# SparkFun_Cellular_Shield.net
KiCad netlist of a schematic drawn in EAGLE
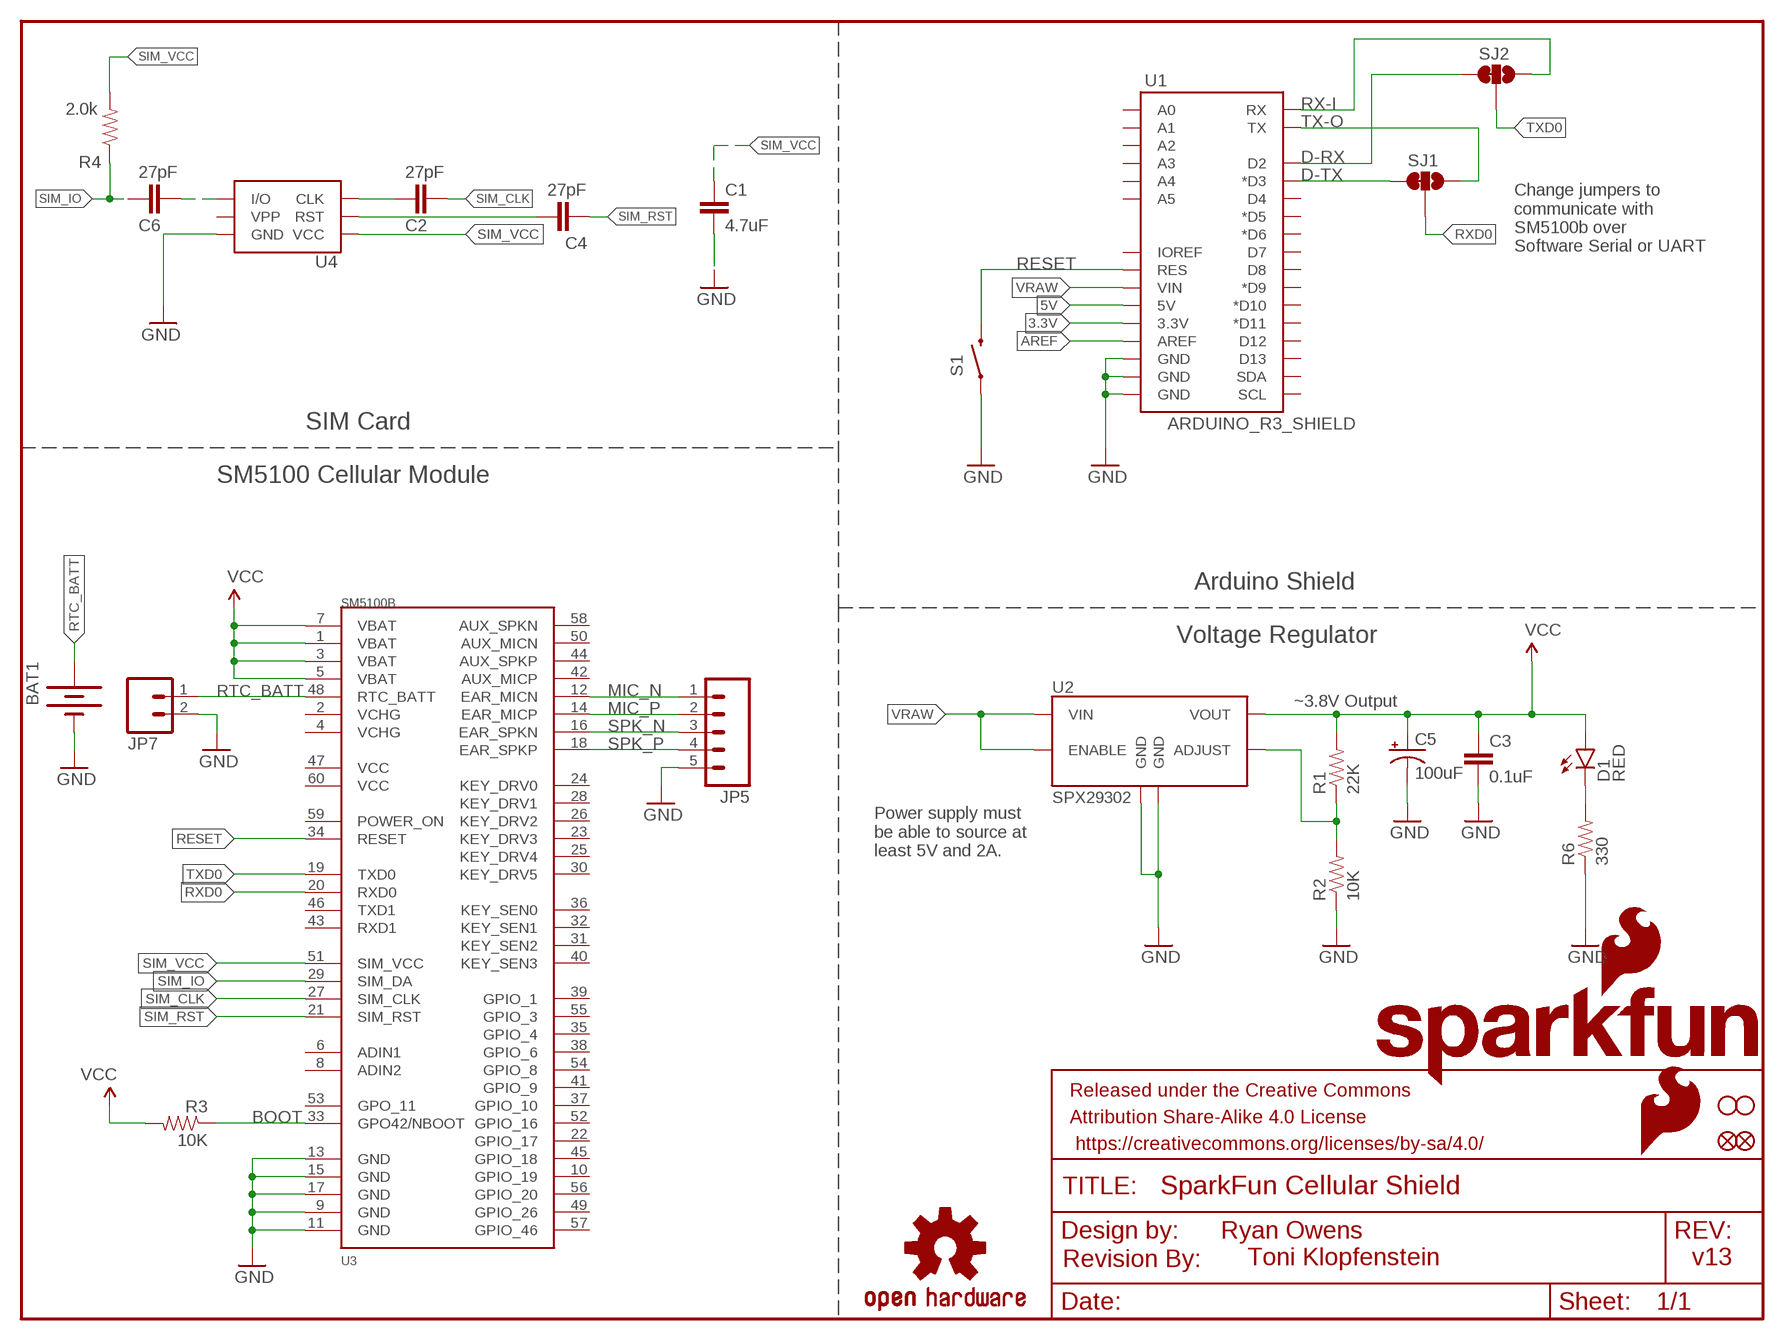
[diagram p0: schematic, sheet 1]

(export (version "E")
  (design (tool "Eeschema 10.0.6"))
  (components
    (comp (ref "BAT1")
      (value "BATTERY20SMD")
      (footprint "eagle-import:BATTCON_20MM")
      (libsource (lib "eagle-import") (part "BATTERY20SMD"))
    )
    (comp (ref "C1")
      (value "4.7uF")
      (footprint "eagle-import:0603-CAP")
      (libsource (lib "eagle-import") (part "4.7UF-6.3V-10%(0603)0603"))
    )
    (comp (ref "C2")
      (value "27pF")
      (footprint "eagle-import:0603-CAP")
      (libsource (lib "eagle-import") (part "27PF50V5%(0603)"))
    )
    (comp (ref "C3")
      (value "0.1uF")
      (footprint "eagle-import:0603-CAP")
      (libsource (lib "eagle-import") (part "0.1UF-25V(+80/-20%)(0603)"))
    )
    (comp (ref "C4")
      (value "27pF")
      (footprint "eagle-import:0603-CAP")
      (libsource (lib "eagle-import") (part "27PF50V5%(0603)"))
    )
    (comp (ref "C5")
      (value "100uF")
      (footprint "eagle-import:EIA7343")
      (libsource (lib "eagle-import") (part "100UF-10V-10%(TANT)"))
    )
    (comp (ref "C6")
      (value "27pF")
      (footprint "eagle-import:0603-CAP")
      (libsource (lib "eagle-import") (part "27PF50V5%(0603)"))
    )
    (comp (ref "D1")
      (value "RED")
      (footprint "eagle-import:LED-0603")
      (libsource (lib "eagle-import") (part "LED-RED0603"))
    )
    (comp (ref "FRAME1")
      (value "FRAME-LETTER")
      (footprint "eagle-import:CREATIVE_COMMONS")
      (libsource (lib "eagle-import") (part "FRAME-LETTER"))
    )
    (comp (ref "JP1")
      (value "SFE_LOGO_NAME_FLAME.2_INCH")
      (footprint "eagle-import:SFE_LOGO_NAME_FLAME_.2")
      (libsource (lib "eagle-import") (part "SFE_LOGO_NAME_FLAME.2_INCH"))
    )
    (comp (ref "JP2")
      (value "FIDUCIAL1X2")
      (footprint "eagle-import:FIDUCIAL-1X2")
      (libsource (lib "eagle-import") (part "FIDUCIAL1X2"))
    )
    (comp (ref "JP3")
      (value "FIDUCIAL1X2")
      (footprint "eagle-import:FIDUCIAL-1X2")
      (libsource (lib "eagle-import") (part "FIDUCIAL1X2"))
    )
    (comp (ref "JP5")
      (value "M05PTH")
      (footprint "eagle-import:1X05")
      (libsource (lib "eagle-import") (part "M05PTH"))
    )
    (comp (ref "JP7")
      (value "M02PTH")
      (footprint "eagle-import:1X02")
      (libsource (lib "eagle-import") (part "M02PTH"))
    )
    (comp (ref "LOGO1")
      (value "OSHW-LOGOM")
      (footprint "eagle-import:OSHW-LOGO-M")
      (libsource (lib "eagle-import") (part "OSHW-LOGOM"))
    )
    (comp (ref "LOGO2")
      (value "SFE_LOGO_FLAME.1_INCH")
      (footprint "eagle-import:SFE_LOGO_FLAME_.1")
      (libsource (lib "eagle-import") (part "SFE_LOGO_FLAME.1_INCH"))
    )
    (comp (ref "R1")
      (value "22K")
      (footprint "eagle-import:0603-RES")
      (libsource (lib "eagle-import") (part "22KOHM1/10W1%(0603)"))
    )
    (comp (ref "R2")
      (value "10K")
      (footprint "eagle-import:0603-RES")
      (libsource (lib "eagle-import") (part "10KOHM-1/10W-1%(0603)0603"))
    )
    (comp (ref "R3")
      (value "10K")
      (footprint "eagle-import:0603-RES")
      (libsource (lib "eagle-import") (part "10KOHM-1/10W-1%(0603)0603"))
    )
    (comp (ref "R4")
      (value "2.0k")
      (footprint "eagle-import:0603-RES")
      (libsource (lib "eagle-import") (part "2.0KOHM1/10W5%(0603)"))
    )
    (comp (ref "R6")
      (value "330")
      (footprint "eagle-import:0603-RES")
      (libsource (lib "eagle-import") (part "330OHM1/10W1%(0603)"))
    )
    (comp (ref "S1")
      (value "TAC_SWITCHSMD")
      (footprint "eagle-import:TACTILE-SWITCH-SMD")
      (libsource (lib "eagle-import") (part "SWITCH-MOMENTARY-2SMD"))
    )
    (comp (ref "SJ1")
      (value "JUMPER-PAD-3-2OF3_NC_BY_TRACE_SMALL")
      (footprint "eagle-import:PAD-JUMPER-3-2OF3_NC_BY_TRACE_YES_SILK_FULL_BOX")
      (libsource (lib "eagle-import") (part "JUMPER-PAD-3-2OF3_NC_BY_TRACE_SMALL"))
    )
    (comp (ref "SJ2")
      (value "JUMPER-PAD-3-2OF3_NC_BY_TRACE_SMALL")
      (footprint "eagle-import:PAD-JUMPER-3-2OF3_NC_BY_TRACE_YES_SILK_FULL_BOX")
      (libsource (lib "eagle-import") (part "JUMPER-PAD-3-2OF3_NC_BY_TRACE_SMALL"))
    )
    (comp (ref "STANDOFF1")
      (value "STAND-OFF")
      (footprint "eagle-import:STAND-OFF")
      (libsource (lib "eagle-import") (part "STAND-OFF"))
    )
    (comp (ref "STANDOFF2")
      (value "STAND-OFF")
      (footprint "eagle-import:STAND-OFF")
      (libsource (lib "eagle-import") (part "STAND-OFF"))
    )
    (comp (ref "U$1")
      (value "REVISION")
      (footprint "eagle-import:REVISION")
      (libsource (lib "eagle-import") (part "REVISION"))
    )
    (comp (ref "U1")
      (value "ARDUINO_R3_SHIELD")
      (footprint "eagle-import:UNO_R3_SHIELD")
      (libsource (lib "eagle-import") (part "ARDUINO_R3_SHIELD"))
    )
    (comp (ref "U2")
      (value "SPX29302")
      (footprint "eagle-import:Q5-DD_SPX29300")
      (libsource (lib "eagle-import") (part "SPX29302"))
    )
    (comp (ref "U3")
      (value "SM5100B")
      (footprint "eagle-import:SM5100B")
      (libsource (lib "eagle-import") (part "SM5100B"))
    )
    (comp (ref "U4")
      (value "SIMHOLDERSIM")
      (footprint "eagle-import:SIMHOLDER")
      (libsource (lib "eagle-import") (part "SIMHOLDERSIM"))
    )
  )
  (nets
    (net (code "1") (name "/BOOT") (class "Default")
      (node (ref "R3") (pin "1") (pinfunction "1_1") (pintype "passive"))
      (node (ref "U3") (pin "33") (pinfunction "GPO42/NBOOT_33") (pintype "bidirectional"))
    )
    (net (code "2") (name "/D-RX") (class "Default")
      (node (ref "SJ2") (pin "3") (pinfunction "3_3") (pintype "passive"))
      (node (ref "U1") (pin "D2") (pinfunction "D2_D2") (pintype "bidirectional"))
    )
    (net (code "3") (name "/D-TX") (class "Default")
      (node (ref "SJ1") (pin "3") (pinfunction "3_3") (pintype "passive"))
      (node (ref "U1") (pin "D3") (pinfunction "*D3_D3") (pintype "bidirectional"))
    )
    (net (code "4") (name "/MIC_N") (class "Default")
      (node (ref "JP5") (pin "1") (pinfunction "1_1") (pintype "passive"))
      (node (ref "U3") (pin "12") (pinfunction "EAR_MICN_12") (pintype "bidirectional"))
    )
    (net (code "5") (name "/MIC_P") (class "Default")
      (node (ref "JP5") (pin "2") (pinfunction "2_2") (pintype "passive"))
      (node (ref "U3") (pin "14") (pinfunction "EAR_MICP_14") (pintype "bidirectional"))
    )
    (net (code "6") (name "/RX-I") (class "Default")
      (node (ref "SJ2") (pin "1") (pinfunction "1_1") (pintype "passive"))
      (node (ref "U1") (pin "RX") (pinfunction "RX_RX") (pintype "bidirectional"))
    )
    (net (code "7") (name "/SPK_N") (class "Default")
      (node (ref "JP5") (pin "3") (pinfunction "3_3") (pintype "passive"))
      (node (ref "U3") (pin "16") (pinfunction "EAR_SPKN_16") (pintype "bidirectional"))
    )
    (net (code "8") (name "/SPK_P") (class "Default")
      (node (ref "JP5") (pin "4") (pinfunction "4_4") (pintype "passive"))
      (node (ref "U3") (pin "18") (pinfunction "EAR_SPKP_18") (pintype "bidirectional"))
    )
    (net (code "9") (name "/TX-O") (class "Default")
      (node (ref "SJ1") (pin "1") (pinfunction "1_1") (pintype "passive"))
      (node (ref "U1") (pin "TX") (pinfunction "TX_TX") (pintype "bidirectional"))
    )
    (net (code "10") (name "3.3V") (class "Default")
      (node (ref "U1") (pin "3.3V") (pinfunction "3.3V_3.3V") (pintype "bidirectional"))
    )
    (net (code "11") (name "5V") (class "Default")
      (node (ref "U1") (pin "5V") (pinfunction "5V_5V") (pintype "bidirectional"))
    )
    (net (code "12") (name "AREF") (class "Default")
      (node (ref "U1") (pin "AREF") (pinfunction "AREF_AREF") (pintype "bidirectional"))
    )
    (net (code "13") (name "GND") (class "Default")
      (node (ref "BAT1") (pin "2") (pinfunction "-_2") (pintype "power_in"))
      (node (ref "C1") (pin "2") (pinfunction "2_2") (pintype "passive"))
      (node (ref "C3") (pin "2") (pinfunction "2_2") (pintype "passive"))
      (node (ref "C5") (pin "C") (pinfunction "-_C") (pintype "passive"))
      (node (ref "JP5") (pin "5") (pinfunction "5_5") (pintype "passive"))
      (node (ref "JP7") (pin "2") (pinfunction "2_2") (pintype "passive"))
      (node (ref "R2") (pin "1") (pinfunction "1_1") (pintype "passive"))
      (node (ref "R6") (pin "1") (pinfunction "1_1") (pintype "passive"))
      (node (ref "S1") (pin "1") (pinfunction "1_1") (pintype "passive"))
      (node (ref "U1") (pin "GND@0") (pinfunction "GND_GND@0") (pintype "bidirectional"))
      (node (ref "U1") (pin "GND@1") (pinfunction "GND_GND@1") (pintype "bidirectional"))
      (node (ref "U1") (pin "GND@2") (pinfunction "GND_GND@2") (pintype "bidirectional"))
      (node (ref "U2") (pin "3") (pinfunction "GND_3") (pintype "bidirectional"))
      (node (ref "U2") (pin "6") (pinfunction "GND_6") (pintype "bidirectional"))
      (node (ref "U3") (pin "11") (pinfunction "GND_11") (pintype "bidirectional"))
      (node (ref "U3") (pin "13") (pinfunction "GND_13") (pintype "bidirectional"))
      (node (ref "U3") (pin "15") (pinfunction "GND_15") (pintype "bidirectional"))
      (node (ref "U3") (pin "17") (pinfunction "GND_17") (pintype "bidirectional"))
      (node (ref "U3") (pin "9") (pinfunction "GND_9") (pintype "bidirectional"))
      (node (ref "U4") (pin "C5") (pinfunction "GND_C5") (pintype "power_in"))
    )
    (net (code "14") (name "Net-(D1-PadC)") (class "Default")
      (node (ref "D1") (pin "C") (pinfunction "C_C") (pintype "passive"))
      (node (ref "R6") (pin "2") (pinfunction "2_2") (pintype "passive"))
    )
    (net (code "15") (name "Net-(U2-ADJUST)") (class "Default")
      (node (ref "R1") (pin "1") (pinfunction "1_1") (pintype "passive"))
      (node (ref "R2") (pin "2") (pinfunction "2_2") (pintype "passive"))
      (node (ref "U2") (pin "5") (pinfunction "ADJUST_5") (pintype "bidirectional"))
    )
    (net (code "16") (name "Net-(U4-CLK)") (class "Default")
      (node (ref "C2") (pin "2") (pinfunction "2_2") (pintype "passive"))
      (node (ref "U4") (pin "C3") (pinfunction "CLK_C3") (pintype "input"))
    )
    (net (code "17") (name "Net-(U4-I{slash}O)") (class "Default")
      (node (ref "C6") (pin "1") (pinfunction "1_1") (pintype "passive"))
      (node (ref "U4") (pin "C7") (pinfunction "I/O_C7") (pintype "bidirectional"))
    )
    (net (code "18") (name "Net-(U4-RST)") (class "Default")
      (node (ref "C4") (pin "2") (pinfunction "2_2") (pintype "passive"))
      (node (ref "U4") (pin "C2") (pinfunction "RST_C2") (pintype "input"))
    )
    (net (code "19") (name "RESET") (class "Default")
      (node (ref "S1") (pin "3") (pinfunction "2_3") (pintype "passive"))
      (node (ref "U1") (pin "RES") (pinfunction "RES_RES") (pintype "bidirectional"))
      (node (ref "U3") (pin "34") (pinfunction "RESET_34") (pintype "bidirectional"))
    )
    (net (code "20") (name "RTC_BATT") (class "Default")
      (node (ref "BAT1") (pin "1") (pinfunction "+_1") (pintype "power_in"))
      (node (ref "JP7") (pin "1") (pinfunction "1_1") (pintype "passive"))
      (node (ref "U3") (pin "48") (pinfunction "RTC_BATT_48") (pintype "bidirectional"))
    )
    (net (code "21") (name "RXD0") (class "Default")
      (node (ref "SJ1") (pin "2") (pinfunction "2_2") (pintype "passive"))
      (node (ref "U3") (pin "20") (pinfunction "RXD0_20") (pintype "bidirectional"))
    )
    (net (code "22") (name "SIM_CLK") (class "Default")
      (node (ref "C2") (pin "1") (pinfunction "1_1") (pintype "passive"))
      (node (ref "U3") (pin "27") (pinfunction "SIM_CLK_27") (pintype "bidirectional"))
    )
    (net (code "23") (name "SIM_IO") (class "Default")
      (node (ref "C6") (pin "2") (pinfunction "2_2") (pintype "passive"))
      (node (ref "R4") (pin "1") (pinfunction "1_1") (pintype "passive"))
      (node (ref "U3") (pin "29") (pinfunction "SIM_DA_29") (pintype "bidirectional"))
    )
    (net (code "24") (name "SIM_RST") (class "Default")
      (node (ref "C4") (pin "1") (pinfunction "1_1") (pintype "passive"))
      (node (ref "U3") (pin "21") (pinfunction "SIM_RST_21") (pintype "bidirectional"))
    )
    (net (code "25") (name "SIM_VCC") (class "Default")
      (node (ref "C1") (pin "1") (pinfunction "1_1") (pintype "passive"))
      (node (ref "R4") (pin "2") (pinfunction "2_2") (pintype "passive"))
      (node (ref "U3") (pin "51") (pinfunction "SIM_VCC_51") (pintype "bidirectional"))
      (node (ref "U4") (pin "C1") (pinfunction "VCC_C1") (pintype "power_in"))
    )
    (net (code "26") (name "TXD0") (class "Default")
      (node (ref "SJ2") (pin "2") (pinfunction "2_2") (pintype "passive"))
      (node (ref "U3") (pin "19") (pinfunction "TXD0_19") (pintype "bidirectional"))
    )
    (net (code "27") (name "VCC") (class "Default")
      (node (ref "C3") (pin "1") (pinfunction "1_1") (pintype "passive"))
      (node (ref "C5") (pin "A") (pinfunction "+_A") (pintype "passive"))
      (node (ref "D1") (pin "A") (pinfunction "A_A") (pintype "passive"))
      (node (ref "R1") (pin "2") (pinfunction "2_2") (pintype "passive"))
      (node (ref "R3") (pin "2") (pinfunction "2_2") (pintype "passive"))
      (node (ref "U2") (pin "4") (pinfunction "VOUT_4") (pintype "bidirectional"))
      (node (ref "U3") (pin "1") (pinfunction "VBAT_1") (pintype "bidirectional"))
      (node (ref "U3") (pin "3") (pinfunction "VBAT_3") (pintype "bidirectional"))
      (node (ref "U3") (pin "5") (pinfunction "VBAT_5") (pintype "bidirectional"))
      (node (ref "U3") (pin "7") (pinfunction "VBAT_7") (pintype "bidirectional"))
    )
    (net (code "28") (name "VRAW") (class "Default")
      (node (ref "U1") (pin "VIN") (pinfunction "VIN_VIN") (pintype "bidirectional"))
      (node (ref "U2") (pin "1") (pinfunction "ENABLE_1") (pintype "bidirectional"))
      (node (ref "U2") (pin "2") (pinfunction "VIN_2") (pintype "bidirectional"))
    )
    (net (code "29") (name "unconnected-(U1-*D5-PadD5)") (class "Default")
      (node (ref "U1") (pin "D5") (pinfunction "*D5_D5") (pintype "bidirectional"))
    )
    (net (code "30") (name "unconnected-(U1-*D6-PadD6)") (class "Default")
      (node (ref "U1") (pin "D6") (pinfunction "*D6_D6") (pintype "bidirectional"))
    )
    (net (code "31") (name "unconnected-(U1-*D9-PadD9)") (class "Default")
      (node (ref "U1") (pin "D9") (pinfunction "*D9_D9") (pintype "bidirectional"))
    )
    (net (code "32") (name "unconnected-(U1-*D10-PadD10)") (class "Default")
      (node (ref "U1") (pin "D10") (pinfunction "*D10_D10") (pintype "bidirectional"))
    )
    (net (code "33") (name "unconnected-(U1-*D11-PadD11)") (class "Default")
      (node (ref "U1") (pin "D11") (pinfunction "*D11_D11") (pintype "bidirectional"))
    )
    (net (code "34") (name "unconnected-(U1-PadA0)") (class "Default")
      (node (ref "U1") (pin "A0") (pinfunction "A0_A0") (pintype "bidirectional"))
    )
    (net (code "35") (name "unconnected-(U1-PadA1)") (class "Default")
      (node (ref "U1") (pin "A1") (pinfunction "A1_A1") (pintype "bidirectional"))
    )
    (net (code "36") (name "unconnected-(U1-PadA2)") (class "Default")
      (node (ref "U1") (pin "A2") (pinfunction "A2_A2") (pintype "bidirectional"))
    )
    (net (code "37") (name "unconnected-(U1-PadA3)") (class "Default")
      (node (ref "U1") (pin "A3") (pinfunction "A3_A3") (pintype "bidirectional"))
    )
    (net (code "38") (name "unconnected-(U1-PadA4)") (class "Default")
      (node (ref "U1") (pin "A4") (pinfunction "A4_A4") (pintype "bidirectional"))
    )
    (net (code "39") (name "unconnected-(U1-PadA5)") (class "Default")
      (node (ref "U1") (pin "A5") (pinfunction "A5_A5") (pintype "bidirectional"))
    )
    (net (code "40") (name "unconnected-(U1-PadD4)") (class "Default")
      (node (ref "U1") (pin "D4") (pinfunction "D4_D4") (pintype "bidirectional"))
    )
    (net (code "41") (name "unconnected-(U1-PadD7)") (class "Default")
      (node (ref "U1") (pin "D7") (pinfunction "D7_D7") (pintype "bidirectional"))
    )
    (net (code "42") (name "unconnected-(U1-PadD8)") (class "Default")
      (node (ref "U1") (pin "D8") (pinfunction "D8_D8") (pintype "bidirectional"))
    )
    (net (code "43") (name "unconnected-(U1-PadD12)") (class "Default")
      (node (ref "U1") (pin "D12") (pinfunction "D12_D12") (pintype "bidirectional"))
    )
    (net (code "44") (name "unconnected-(U1-PadD13)") (class "Default")
      (node (ref "U1") (pin "D13") (pinfunction "D13_D13") (pintype "bidirectional"))
    )
    (net (code "45") (name "unconnected-(U1-PadIOREF)") (class "Default")
      (node (ref "U1") (pin "IOREF") (pinfunction "IOREF_IOREF") (pintype "bidirectional"))
    )
    (net (code "46") (name "unconnected-(U1-PadSCL)") (class "Default")
      (node (ref "U1") (pin "SCL") (pinfunction "SCL_SCL") (pintype "bidirectional"))
    )
    (net (code "47") (name "unconnected-(U1-PadSDA)") (class "Default")
      (node (ref "U1") (pin "SDA") (pinfunction "SDA_SDA") (pintype "bidirectional"))
    )
    (net (code "48") (name "unconnected-(U3-ADIN1-Pad6)") (class "Default")
      (node (ref "U3") (pin "6") (pinfunction "ADIN1_6") (pintype "bidirectional"))
    )
    (net (code "49") (name "unconnected-(U3-ADIN2-Pad8)") (class "Default")
      (node (ref "U3") (pin "8") (pinfunction "ADIN2_8") (pintype "bidirectional"))
    )
    (net (code "50") (name "unconnected-(U3-AUX_MICN-Pad50)") (class "Default")
      (node (ref "U3") (pin "50") (pinfunction "AUX_MICN_50") (pintype "bidirectional"))
    )
    (net (code "51") (name "unconnected-(U3-AUX_MICP-Pad42)") (class "Default")
      (node (ref "U3") (pin "42") (pinfunction "AUX_MICP_42") (pintype "bidirectional"))
    )
    (net (code "52") (name "unconnected-(U3-AUX_SPKN-Pad58)") (class "Default")
      (node (ref "U3") (pin "58") (pinfunction "AUX_SPKN_58") (pintype "bidirectional"))
    )
    (net (code "53") (name "unconnected-(U3-AUX_SPKP-Pad44)") (class "Default")
      (node (ref "U3") (pin "44") (pinfunction "AUX_SPKP_44") (pintype "bidirectional"))
    )
    (net (code "54") (name "unconnected-(U3-GPIO_1-Pad39)") (class "Default")
      (node (ref "U3") (pin "39") (pinfunction "GPIO_1_39") (pintype "bidirectional"))
    )
    (net (code "55") (name "unconnected-(U3-GPIO_3-Pad55)") (class "Default")
      (node (ref "U3") (pin "55") (pinfunction "GPIO_3_55") (pintype "bidirectional"))
    )
    (net (code "56") (name "unconnected-(U3-GPIO_4-Pad35)") (class "Default")
      (node (ref "U3") (pin "35") (pinfunction "GPIO_4_35") (pintype "bidirectional"))
    )
    (net (code "57") (name "unconnected-(U3-GPIO_6-Pad38)") (class "Default")
      (node (ref "U3") (pin "38") (pinfunction "GPIO_6_38") (pintype "bidirectional"))
    )
    (net (code "58") (name "unconnected-(U3-GPIO_8-Pad54)") (class "Default")
      (node (ref "U3") (pin "54") (pinfunction "GPIO_8_54") (pintype "bidirectional"))
    )
    (net (code "59") (name "unconnected-(U3-GPIO_9-Pad41)") (class "Default")
      (node (ref "U3") (pin "41") (pinfunction "GPIO_9_41") (pintype "bidirectional"))
    )
    (net (code "60") (name "unconnected-(U3-GPIO_10-Pad37)") (class "Default")
      (node (ref "U3") (pin "37") (pinfunction "GPIO_10_37") (pintype "bidirectional"))
    )
    (net (code "61") (name "unconnected-(U3-GPIO_16-Pad52)") (class "Default")
      (node (ref "U3") (pin "52") (pinfunction "GPIO_16_52") (pintype "bidirectional"))
    )
    (net (code "62") (name "unconnected-(U3-GPIO_17-Pad22)") (class "Default")
      (node (ref "U3") (pin "22") (pinfunction "GPIO_17_22") (pintype "bidirectional"))
    )
    (net (code "63") (name "unconnected-(U3-GPIO_18-Pad45)") (class "Default")
      (node (ref "U3") (pin "45") (pinfunction "GPIO_18_45") (pintype "bidirectional"))
    )
    (net (code "64") (name "unconnected-(U3-GPIO_19-Pad10)") (class "Default")
      (node (ref "U3") (pin "10") (pinfunction "GPIO_19_10") (pintype "bidirectional"))
    )
    (net (code "65") (name "unconnected-(U3-GPIO_20-Pad56)") (class "Default")
      (node (ref "U3") (pin "56") (pinfunction "GPIO_20_56") (pintype "bidirectional"))
    )
    (net (code "66") (name "unconnected-(U3-GPIO_26-Pad49)") (class "Default")
      (node (ref "U3") (pin "49") (pinfunction "GPIO_26_49") (pintype "bidirectional"))
    )
    (net (code "67") (name "unconnected-(U3-GPIO_46-Pad57)") (class "Default")
      (node (ref "U3") (pin "57") (pinfunction "GPIO_46_57") (pintype "bidirectional"))
    )
    (net (code "68") (name "unconnected-(U3-GPO_11-Pad53)") (class "Default")
      (node (ref "U3") (pin "53") (pinfunction "GPO_11_53") (pintype "bidirectional"))
    )
    (net (code "69") (name "unconnected-(U3-KEY_DRV0-Pad24)") (class "Default")
      (node (ref "U3") (pin "24") (pinfunction "KEY_DRV0_24") (pintype "bidirectional"))
    )
    (net (code "70") (name "unconnected-(U3-KEY_DRV1-Pad28)") (class "Default")
      (node (ref "U3") (pin "28") (pinfunction "KEY_DRV1_28") (pintype "bidirectional"))
    )
    (net (code "71") (name "unconnected-(U3-KEY_DRV2-Pad26)") (class "Default")
      (node (ref "U3") (pin "26") (pinfunction "KEY_DRV2_26") (pintype "bidirectional"))
    )
    (net (code "72") (name "unconnected-(U3-KEY_DRV3-Pad23)") (class "Default")
      (node (ref "U3") (pin "23") (pinfunction "KEY_DRV3_23") (pintype "bidirectional"))
    )
    (net (code "73") (name "unconnected-(U3-KEY_DRV4-Pad25)") (class "Default")
      (node (ref "U3") (pin "25") (pinfunction "KEY_DRV4_25") (pintype "bidirectional"))
    )
    (net (code "74") (name "unconnected-(U3-KEY_DRV5-Pad30)") (class "Default")
      (node (ref "U3") (pin "30") (pinfunction "KEY_DRV5_30") (pintype "bidirectional"))
    )
    (net (code "75") (name "unconnected-(U3-KEY_SEN0-Pad36)") (class "Default")
      (node (ref "U3") (pin "36") (pinfunction "KEY_SEN0_36") (pintype "bidirectional"))
    )
    (net (code "76") (name "unconnected-(U3-KEY_SEN1-Pad32)") (class "Default")
      (node (ref "U3") (pin "32") (pinfunction "KEY_SEN1_32") (pintype "bidirectional"))
    )
    (net (code "77") (name "unconnected-(U3-KEY_SEN2-Pad31)") (class "Default")
      (node (ref "U3") (pin "31") (pinfunction "KEY_SEN2_31") (pintype "bidirectional"))
    )
    (net (code "78") (name "unconnected-(U3-KEY_SEN3-Pad40)") (class "Default")
      (node (ref "U3") (pin "40") (pinfunction "KEY_SEN3_40") (pintype "bidirectional"))
    )
    (net (code "79") (name "unconnected-(U3-POWER_ON-Pad59)") (class "Default")
      (node (ref "U3") (pin "59") (pinfunction "POWER_ON_59") (pintype "bidirectional"))
    )
    (net (code "80") (name "unconnected-(U3-RXD1-Pad43)") (class "Default")
      (node (ref "U3") (pin "43") (pinfunction "RXD1_43") (pintype "bidirectional"))
    )
    (net (code "81") (name "unconnected-(U3-TXD1-Pad46)") (class "Default")
      (node (ref "U3") (pin "46") (pinfunction "TXD1_46") (pintype "bidirectional"))
    )
    (net (code "82") (name "unconnected-(U3-VCC-Pad47)") (class "Default")
      (node (ref "U3") (pin "47") (pinfunction "VCC_47") (pintype "bidirectional"))
    )
    (net (code "83") (name "unconnected-(U3-VCC-Pad60)") (class "Default")
      (node (ref "U3") (pin "60") (pinfunction "VCC_60") (pintype "bidirectional"))
    )
    (net (code "84") (name "unconnected-(U3-VCHG-Pad2)") (class "Default")
      (node (ref "U3") (pin "2") (pinfunction "VCHG_2") (pintype "bidirectional"))
    )
    (net (code "85") (name "unconnected-(U3-VCHG-Pad4)") (class "Default")
      (node (ref "U3") (pin "4") (pinfunction "VCHG_4") (pintype "bidirectional"))
    )
    (net (code "86") (name "unconnected-(U4-VPP-PadC6)") (class "Default")
      (node (ref "U4") (pin "C6") (pinfunction "VPP_C6") (pintype "input"))
    )
  )
)
